# Saturn_Cartage.net
KiCad netlist of a schematic drawn in Altium Designer
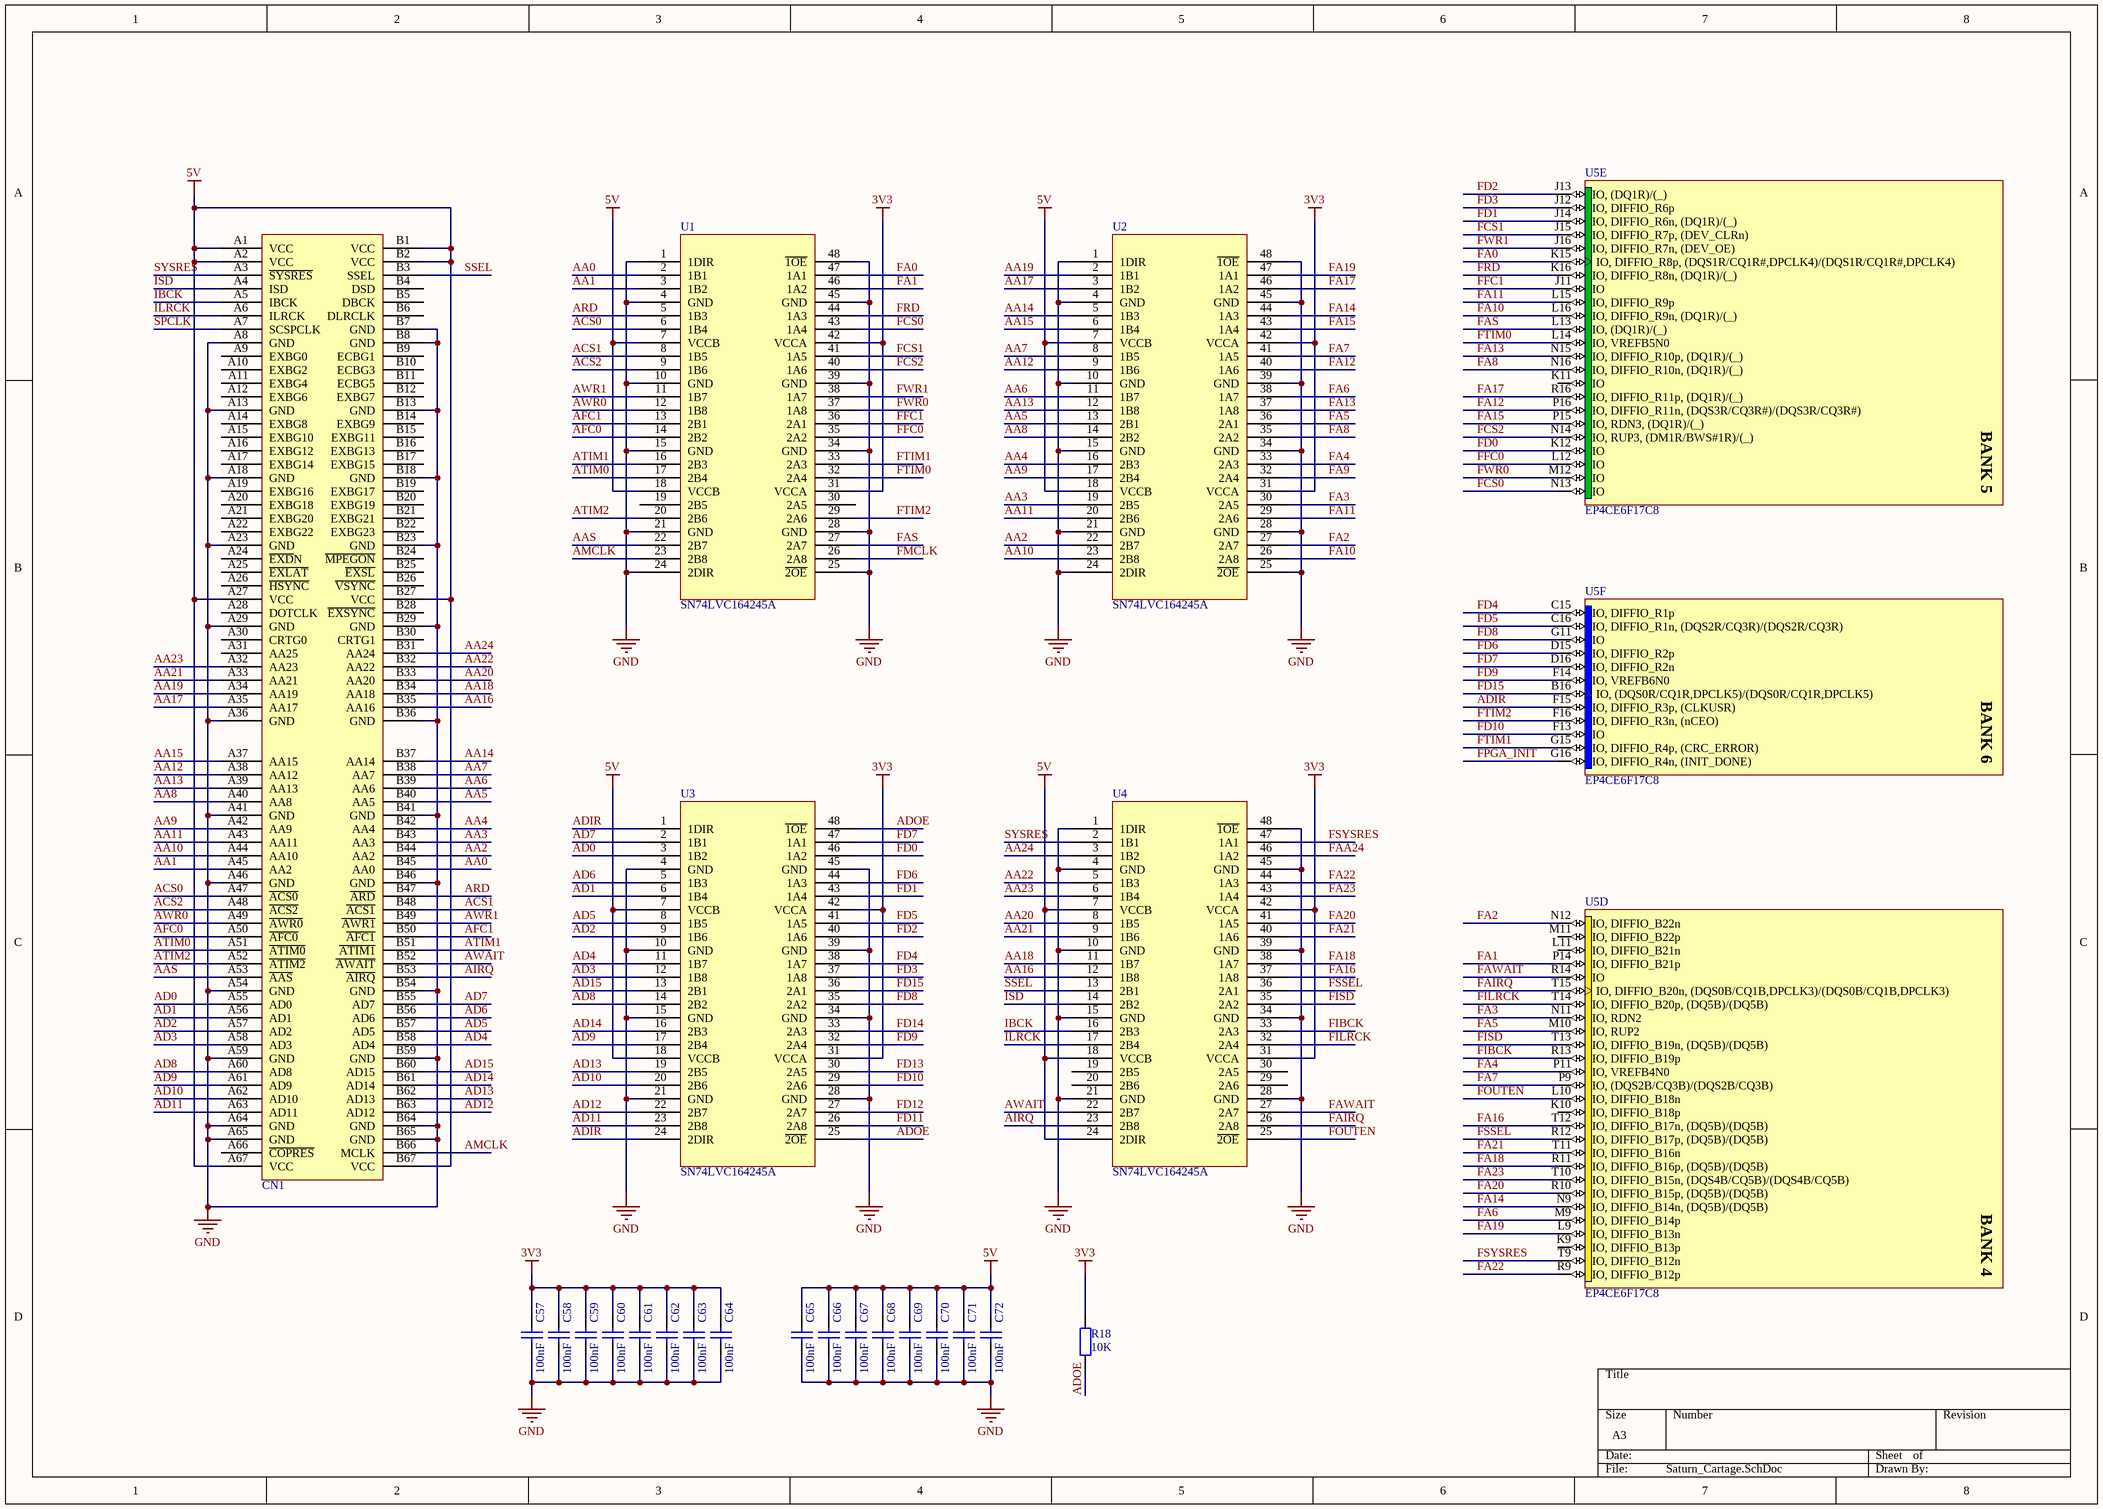
[diagram p0: Saturn_Cartage.SchDoc]

(export (version "E")
  (design (tool "Eeschema 10.0.6"))
  (components
    (comp (ref "C57")
      (value "100nF")
      (footprint "C0603")
      (description "Capacitor")
      (fields (field (name "PUBLISHER") "Altium Limited"))
      (libsource (lib "Miscellaneous Devices") (part "Cap"))
    )
    (comp (ref "C58")
      (value "100nF")
      (footprint "C0603")
      (description "Capacitor")
      (fields (field (name "PUBLISHER") "Altium Limited"))
      (libsource (lib "Miscellaneous Devices") (part "Cap"))
    )
    (comp (ref "C59")
      (value "100nF")
      (footprint "C0603")
      (description "Capacitor")
      (fields (field (name "PUBLISHER") "Altium Limited"))
      (libsource (lib "Miscellaneous Devices") (part "Cap"))
    )
    (comp (ref "C60")
      (value "100nF")
      (footprint "C0603")
      (description "Capacitor")
      (fields (field (name "PUBLISHER") "Altium Limited"))
      (libsource (lib "Miscellaneous Devices") (part "Cap"))
    )
    (comp (ref "C61")
      (value "100nF")
      (footprint "C0603")
      (description "Capacitor")
      (fields (field (name "PUBLISHER") "Altium Limited"))
      (libsource (lib "Miscellaneous Devices") (part "Cap"))
    )
    (comp (ref "C62")
      (value "100nF")
      (footprint "C0603")
      (description "Capacitor")
      (fields (field (name "PUBLISHER") "Altium Limited"))
      (libsource (lib "Miscellaneous Devices") (part "Cap"))
    )
    (comp (ref "C63")
      (value "100nF")
      (footprint "C0603")
      (description "Capacitor")
      (fields (field (name "PUBLISHER") "Altium Limited"))
      (libsource (lib "Miscellaneous Devices") (part "Cap"))
    )
    (comp (ref "C64")
      (value "100nF")
      (footprint "C0603")
      (description "Capacitor")
      (fields (field (name "PUBLISHER") "Altium Limited"))
      (libsource (lib "Miscellaneous Devices") (part "Cap"))
    )
    (comp (ref "C65")
      (value "100nF")
      (footprint "C0603")
      (description "Capacitor")
      (fields (field (name "PUBLISHER") "Altium Limited"))
      (libsource (lib "Miscellaneous Devices") (part "Cap"))
    )
    (comp (ref "C66")
      (value "100nF")
      (footprint "C0603")
      (description "Capacitor")
      (fields (field (name "PUBLISHER") "Altium Limited"))
      (libsource (lib "Miscellaneous Devices") (part "Cap"))
    )
    (comp (ref "C67")
      (value "100nF")
      (footprint "C0603")
      (description "Capacitor")
      (fields (field (name "PUBLISHER") "Altium Limited"))
      (libsource (lib "Miscellaneous Devices") (part "Cap"))
    )
    (comp (ref "C68")
      (value "100nF")
      (footprint "C0603")
      (description "Capacitor")
      (fields (field (name "PUBLISHER") "Altium Limited"))
      (libsource (lib "Miscellaneous Devices") (part "Cap"))
    )
    (comp (ref "C69")
      (value "100nF")
      (footprint "C0603")
      (description "Capacitor")
      (fields (field (name "PUBLISHER") "Altium Limited"))
      (libsource (lib "Miscellaneous Devices") (part "Cap"))
    )
    (comp (ref "C70")
      (value "100nF")
      (footprint "C0603")
      (description "Capacitor")
      (fields (field (name "PUBLISHER") "Altium Limited"))
      (libsource (lib "Miscellaneous Devices") (part "Cap"))
    )
    (comp (ref "C71")
      (value "100nF")
      (footprint "C0603")
      (description "Capacitor")
      (fields (field (name "PUBLISHER") "Altium Limited"))
      (libsource (lib "Miscellaneous Devices") (part "Cap"))
    )
    (comp (ref "C72")
      (value "100nF")
      (footprint "C0603")
      (description "Capacitor")
      (fields (field (name "PUBLISHER") "Altium Limited"))
      (libsource (lib "Miscellaneous Devices") (part "Cap"))
    )
    (comp (ref "CN1")
      (value "SaturnCartage")
      (footprint "Saturn_cart")
      (libsource (lib "ssmaster_1") (part "SaturnCartage"))
    )
    (comp (ref "R18")
      (value "10K")
      (footprint "R0603")
      (description "Resistor")
      (fields (field (name "PUBLISHER") "Altium Limited"))
      (libsource (lib "Miscellaneous Devices") (part "Res2"))
    )
    (comp (ref "U1")
      (value "SN74LVC164245A")
      (footprint "DGG048")
      (libsource (lib "ssmaster_1") (part "SN74LVC164245A"))
    )
    (comp (ref "U2")
      (value "SN74LVC164245A")
      (footprint "DGG048")
      (libsource (lib "ssmaster_1") (part "SN74LVC164245A"))
    )
    (comp (ref "U3")
      (value "SN74LVC164245A")
      (footprint "DGG048")
      (libsource (lib "ssmaster_1") (part "SN74LVC164245A"))
    )
    (comp (ref "U4")
      (value "SN74LVC164245A")
      (footprint "DGG048")
      (libsource (lib "ssmaster_1") (part "SN74LVC164245A"))
    )
    (comp (ref "U5")
      (value "EP4CE6F17C8")
      (footprint "FBGA256")
      (fields (field (name "PUBLISHER") "Altium Limited"))
      (libsource (lib "Altera Cyclone IV E") (part "EP4CE6F17C8"))
    )
  )
  (nets
    (net (code "1") (name "/AA0") (class "Default")
      (node (ref "CN1") (pin "B45") (pinfunction "AA0_B45") (pintype "passive"))
      (node (ref "U1") (pin "2") (pinfunction "1B1_2") (pintype "passive"))
    )
    (net (code "2") (name "/AA1") (class "Default")
      (node (ref "CN1") (pin "A45") (pinfunction "AA2_A45") (pintype "passive"))
      (node (ref "U1") (pin "3") (pinfunction "1B2_3") (pintype "passive"))
    )
    (net (code "3") (name "/AA2") (class "Default")
      (node (ref "CN1") (pin "B44") (pinfunction "AA2_B44") (pintype "passive"))
      (node (ref "U2") (pin "22") (pinfunction "2B7_22") (pintype "passive"))
    )
    (net (code "4") (name "/AA3") (class "Default")
      (node (ref "CN1") (pin "B43") (pinfunction "AA3_B43") (pintype "passive"))
      (node (ref "U2") (pin "19") (pinfunction "2B5_19") (pintype "passive"))
    )
    (net (code "5") (name "/AA4") (class "Default")
      (node (ref "CN1") (pin "B42") (pinfunction "AA4_B42") (pintype "passive"))
      (node (ref "U2") (pin "16") (pinfunction "2B3_16") (pintype "passive"))
    )
    (net (code "6") (name "/AA5") (class "Default")
      (node (ref "CN1") (pin "B40") (pinfunction "AA5_B40") (pintype "passive"))
      (node (ref "U2") (pin "13") (pinfunction "2B1_13") (pintype "passive"))
    )
    (net (code "7") (name "/AA6") (class "Default")
      (node (ref "CN1") (pin "B39") (pinfunction "AA6_B39") (pintype "passive"))
      (node (ref "U2") (pin "11") (pinfunction "1B7_11") (pintype "passive"))
    )
    (net (code "8") (name "/AA7") (class "Default")
      (node (ref "CN1") (pin "B38") (pinfunction "AA7_B38") (pintype "passive"))
      (node (ref "U2") (pin "8") (pinfunction "1B5_8") (pintype "passive"))
    )
    (net (code "9") (name "/AA8") (class "Default")
      (node (ref "CN1") (pin "A40") (pinfunction "AA8_A40") (pintype "passive"))
      (node (ref "U2") (pin "14") (pinfunction "2B2_14") (pintype "passive"))
    )
    (net (code "10") (name "/AA9") (class "Default")
      (node (ref "CN1") (pin "A42") (pinfunction "AA9_A42") (pintype "passive"))
      (node (ref "U2") (pin "17") (pinfunction "2B4_17") (pintype "passive"))
    )
    (net (code "11") (name "/AA10") (class "Default")
      (node (ref "CN1") (pin "A44") (pinfunction "AA10_A44") (pintype "passive"))
      (node (ref "U2") (pin "23") (pinfunction "2B8_23") (pintype "passive"))
    )
    (net (code "12") (name "/AA11") (class "Default")
      (node (ref "CN1") (pin "A43") (pinfunction "AA11_A43") (pintype "passive"))
      (node (ref "U2") (pin "20") (pinfunction "2B6_20") (pintype "passive"))
    )
    (net (code "13") (name "/AA12") (class "Default")
      (node (ref "CN1") (pin "A38") (pinfunction "AA12_A38") (pintype "passive"))
      (node (ref "U2") (pin "9") (pinfunction "1B6_9") (pintype "passive"))
    )
    (net (code "14") (name "/AA13") (class "Default")
      (node (ref "CN1") (pin "A39") (pinfunction "AA13_A39") (pintype "passive"))
      (node (ref "U2") (pin "12") (pinfunction "1B8_12") (pintype "passive"))
    )
    (net (code "15") (name "/AA14") (class "Default")
      (node (ref "CN1") (pin "B37") (pinfunction "AA14_B37") (pintype "passive"))
      (node (ref "U2") (pin "5") (pinfunction "1B3_5") (pintype "passive"))
    )
    (net (code "16") (name "/AA15") (class "Default")
      (node (ref "CN1") (pin "A37") (pinfunction "AA15_A37") (pintype "passive"))
      (node (ref "U2") (pin "6") (pinfunction "1B4_6") (pintype "passive"))
    )
    (net (code "17") (name "/AA16") (class "Default")
      (node (ref "CN1") (pin "B35") (pinfunction "AA16_B35") (pintype "passive"))
      (node (ref "U4") (pin "12") (pinfunction "1B8_12") (pintype "passive"))
    )
    (net (code "18") (name "/AA17") (class "Default")
      (node (ref "CN1") (pin "A35") (pinfunction "AA17_A35") (pintype "passive"))
      (node (ref "U2") (pin "3") (pinfunction "1B2_3") (pintype "passive"))
    )
    (net (code "19") (name "/AA18") (class "Default")
      (node (ref "CN1") (pin "B34") (pinfunction "AA18_B34") (pintype "passive"))
      (node (ref "U4") (pin "11") (pinfunction "1B7_11") (pintype "passive"))
    )
    (net (code "20") (name "/AA19") (class "Default")
      (node (ref "CN1") (pin "A34") (pinfunction "AA19_A34") (pintype "passive"))
      (node (ref "U2") (pin "2") (pinfunction "1B1_2") (pintype "passive"))
    )
    (net (code "21") (name "/AA20") (class "Default")
      (node (ref "CN1") (pin "B33") (pinfunction "AA20_B33") (pintype "passive"))
      (node (ref "U4") (pin "8") (pinfunction "1B5_8") (pintype "passive"))
    )
    (net (code "22") (name "/AA21") (class "Default")
      (node (ref "CN1") (pin "A33") (pinfunction "AA21_A33") (pintype "passive"))
      (node (ref "U4") (pin "9") (pinfunction "1B6_9") (pintype "passive"))
    )
    (net (code "23") (name "/AA22") (class "Default")
      (node (ref "CN1") (pin "B32") (pinfunction "AA22_B32") (pintype "passive"))
      (node (ref "U4") (pin "5") (pinfunction "1B3_5") (pintype "passive"))
    )
    (net (code "24") (name "/AA23") (class "Default")
      (node (ref "CN1") (pin "A32") (pinfunction "AA23_A32") (pintype "passive"))
      (node (ref "U4") (pin "6") (pinfunction "1B4_6") (pintype "passive"))
    )
    (net (code "25") (name "/AA24") (class "Default")
      (node (ref "CN1") (pin "B31") (pinfunction "AA24_B31") (pintype "passive"))
      (node (ref "U4") (pin "3") (pinfunction "1B2_3") (pintype "passive"))
    )
    (net (code "26") (name "/AAS") (class "Default")
      (node (ref "CN1") (pin "A53") (pinfunction "~{AAS}_A53") (pintype "passive"))
      (node (ref "U1") (pin "22") (pinfunction "2B7_22") (pintype "passive"))
    )
    (net (code "27") (name "/ACS0") (class "Default")
      (node (ref "CN1") (pin "A47") (pinfunction "~{ACS0}_A47") (pintype "passive"))
      (node (ref "U1") (pin "6") (pinfunction "1B4_6") (pintype "passive"))
    )
    (net (code "28") (name "/ACS1") (class "Default")
      (node (ref "CN1") (pin "B48") (pinfunction "~{ACS1}_B48") (pintype "passive"))
      (node (ref "U1") (pin "8") (pinfunction "1B5_8") (pintype "passive"))
    )
    (net (code "29") (name "/ACS2") (class "Default")
      (node (ref "CN1") (pin "A48") (pinfunction "~{ACS2}_A48") (pintype "passive"))
      (node (ref "U1") (pin "9") (pinfunction "1B6_9") (pintype "passive"))
    )
    (net (code "30") (name "/AD0") (class "Default")
      (node (ref "CN1") (pin "A55") (pinfunction "AD0_A55") (pintype "passive"))
      (node (ref "U3") (pin "3") (pinfunction "1B2_3") (pintype "passive"))
    )
    (net (code "31") (name "/AD1") (class "Default")
      (node (ref "CN1") (pin "A56") (pinfunction "AD1_A56") (pintype "passive"))
      (node (ref "U3") (pin "6") (pinfunction "1B4_6") (pintype "passive"))
    )
    (net (code "32") (name "/AD2") (class "Default")
      (node (ref "CN1") (pin "A57") (pinfunction "AD2_A57") (pintype "passive"))
      (node (ref "U3") (pin "9") (pinfunction "1B6_9") (pintype "passive"))
    )
    (net (code "33") (name "/AD3") (class "Default")
      (node (ref "CN1") (pin "A58") (pinfunction "AD3_A58") (pintype "passive"))
      (node (ref "U3") (pin "12") (pinfunction "1B8_12") (pintype "passive"))
    )
    (net (code "34") (name "/AD4") (class "Default")
      (node (ref "CN1") (pin "B58") (pinfunction "AD4_B58") (pintype "passive"))
      (node (ref "U3") (pin "11") (pinfunction "1B7_11") (pintype "passive"))
    )
    (net (code "35") (name "/AD5") (class "Default")
      (node (ref "CN1") (pin "B57") (pinfunction "AD5_B57") (pintype "passive"))
      (node (ref "U3") (pin "8") (pinfunction "1B5_8") (pintype "passive"))
    )
    (net (code "36") (name "/AD6") (class "Default")
      (node (ref "CN1") (pin "B56") (pinfunction "AD6_B56") (pintype "passive"))
      (node (ref "U3") (pin "5") (pinfunction "1B3_5") (pintype "passive"))
    )
    (net (code "37") (name "/AD7") (class "Default")
      (node (ref "CN1") (pin "B55") (pinfunction "AD7_B55") (pintype "passive"))
      (node (ref "U3") (pin "2") (pinfunction "1B1_2") (pintype "passive"))
    )
    (net (code "38") (name "/AD8") (class "Default")
      (node (ref "CN1") (pin "A60") (pinfunction "AD8_A60") (pintype "passive"))
      (node (ref "U3") (pin "14") (pinfunction "2B2_14") (pintype "passive"))
    )
    (net (code "39") (name "/AD9") (class "Default")
      (node (ref "CN1") (pin "A61") (pinfunction "AD9_A61") (pintype "passive"))
      (node (ref "U3") (pin "17") (pinfunction "2B4_17") (pintype "passive"))
    )
    (net (code "40") (name "/AD10") (class "Default")
      (node (ref "CN1") (pin "A62") (pinfunction "AD10_A62") (pintype "passive"))
      (node (ref "U3") (pin "20") (pinfunction "2B6_20") (pintype "passive"))
    )
    (net (code "41") (name "/AD11") (class "Default")
      (node (ref "CN1") (pin "A63") (pinfunction "AD11_A63") (pintype "passive"))
      (node (ref "U3") (pin "23") (pinfunction "2B8_23") (pintype "passive"))
    )
    (net (code "42") (name "/AD12") (class "Default")
      (node (ref "CN1") (pin "B63") (pinfunction "AD12_B63") (pintype "passive"))
      (node (ref "U3") (pin "22") (pinfunction "2B7_22") (pintype "passive"))
    )
    (net (code "43") (name "/AD13") (class "Default")
      (node (ref "CN1") (pin "B62") (pinfunction "AD13_B62") (pintype "passive"))
      (node (ref "U3") (pin "19") (pinfunction "2B5_19") (pintype "passive"))
    )
    (net (code "44") (name "/AD14") (class "Default")
      (node (ref "CN1") (pin "B61") (pinfunction "AD14_B61") (pintype "passive"))
      (node (ref "U3") (pin "16") (pinfunction "2B3_16") (pintype "passive"))
    )
    (net (code "45") (name "/AD15") (class "Default")
      (node (ref "CN1") (pin "B60") (pinfunction "AD15_B60") (pintype "passive"))
      (node (ref "U3") (pin "13") (pinfunction "2B1_13") (pintype "passive"))
    )
    (net (code "46") (name "/ADIR") (class "Default")
      (node (ref "U3") (pin "1") (pinfunction "1DIR_1") (pintype "passive"))
      (node (ref "U3") (pin "24") (pinfunction "2DIR_24") (pintype "passive"))
      (node (ref "U5") (pin "F15") (pinfunction "IO,_DIFFIO_R3p,_(CLKUSR)_F15") (pintype "bidirectional"))
    )
    (net (code "47") (name "/ADOE") (class "Default")
      (node (ref "R18") (pin "1") (pinfunction "1_1") (pintype "passive"))
      (node (ref "U3") (pin "25") (pinfunction "~{2OE}_25") (pintype "passive"))
      (node (ref "U3") (pin "48") (pinfunction "~{1OE}_48") (pintype "passive"))
    )
    (net (code "48") (name "/AFC0") (class "Default")
      (node (ref "CN1") (pin "A50") (pinfunction "~{AFC0}_A50") (pintype "passive"))
      (node (ref "U1") (pin "14") (pinfunction "2B2_14") (pintype "passive"))
    )
    (net (code "49") (name "/AFC1") (class "Default")
      (node (ref "CN1") (pin "B50") (pinfunction "~{AFC1}_B50") (pintype "passive"))
      (node (ref "U1") (pin "13") (pinfunction "2B1_13") (pintype "passive"))
    )
    (net (code "50") (name "/AIRQ") (class "Default")
      (node (ref "CN1") (pin "B53") (pinfunction "~{AIRQ}_B53") (pintype "passive"))
      (node (ref "U4") (pin "23") (pinfunction "2B8_23") (pintype "passive"))
    )
    (net (code "51") (name "/AMCLK") (class "Default")
      (node (ref "CN1") (pin "B66") (pinfunction "MCLK_B66") (pintype "passive"))
      (node (ref "U1") (pin "23") (pinfunction "2B8_23") (pintype "passive"))
    )
    (net (code "52") (name "/ARD") (class "Default")
      (node (ref "CN1") (pin "B47") (pinfunction "~{ARD}_B47") (pintype "passive"))
      (node (ref "U1") (pin "5") (pinfunction "1B3_5") (pintype "passive"))
    )
    (net (code "53") (name "/ATIM0") (class "Default")
      (node (ref "CN1") (pin "A51") (pinfunction "~{ATIM0}_A51") (pintype "passive"))
      (node (ref "U1") (pin "17") (pinfunction "2B4_17") (pintype "passive"))
    )
    (net (code "54") (name "/ATIM1") (class "Default")
      (node (ref "CN1") (pin "B51") (pinfunction "~{ATIM1}_B51") (pintype "passive"))
      (node (ref "U1") (pin "16") (pinfunction "2B3_16") (pintype "passive"))
    )
    (net (code "55") (name "/ATIM2") (class "Default")
      (node (ref "CN1") (pin "A52") (pinfunction "~{ATIM2}_A52") (pintype "passive"))
      (node (ref "U1") (pin "20") (pinfunction "2B6_20") (pintype "passive"))
    )
    (net (code "56") (name "/AWAIT") (class "Default")
      (node (ref "CN1") (pin "B52") (pinfunction "~{AWAIT}_B52") (pintype "passive"))
      (node (ref "U4") (pin "22") (pinfunction "2B7_22") (pintype "passive"))
    )
    (net (code "57") (name "/AWR0") (class "Default")
      (node (ref "CN1") (pin "A49") (pinfunction "~{AWR0}_A49") (pintype "passive"))
      (node (ref "U1") (pin "12") (pinfunction "1B8_12") (pintype "passive"))
    )
    (net (code "58") (name "/AWR1") (class "Default")
      (node (ref "CN1") (pin "B49") (pinfunction "~{AWR1}_B49") (pintype "passive"))
      (node (ref "U1") (pin "11") (pinfunction "1B7_11") (pintype "passive"))
    )
    (net (code "59") (name "/FA0") (class "Default")
      (node (ref "U1") (pin "47") (pinfunction "1A1_47") (pintype "passive"))
      (node (ref "U5") (pin "K15") (pinfunction "IO,_DIFFIO_R8p,_(DQS1R/CQ1R#,DPCLK4)/(DQS1R/CQ1R#,DPCLK4)_K15") (pintype "bidirectional"))
    )
    (net (code "60") (name "/FA1") (class "Default")
      (node (ref "U1") (pin "46") (pinfunction "1A2_46") (pintype "power_in"))
      (node (ref "U5") (pin "P14") (pinfunction "IO,_DIFFIO_B21p_P14") (pintype "bidirectional"))
    )
    (net (code "61") (name "/FA2") (class "Default")
      (node (ref "U2") (pin "27") (pinfunction "2A7_27") (pintype "passive"))
      (node (ref "U5") (pin "N12") (pinfunction "IO,_DIFFIO_B22n_N12") (pintype "bidirectional"))
    )
    (net (code "62") (name "/FA3") (class "Default")
      (node (ref "U2") (pin "30") (pinfunction "2A5_30") (pintype "passive"))
      (node (ref "U5") (pin "N11") (pinfunction "IO,_RDN2_N11") (pintype "bidirectional"))
    )
    (net (code "63") (name "/FA4") (class "Default")
      (node (ref "U2") (pin "33") (pinfunction "2A3_33") (pintype "passive"))
      (node (ref "U5") (pin "P11") (pinfunction "IO,_VREFB4N0_P11") (pintype "bidirectional"))
    )
    (net (code "64") (name "/FA5") (class "Default")
      (node (ref "U2") (pin "36") (pinfunction "2A1_36") (pintype "passive"))
      (node (ref "U5") (pin "M10") (pinfunction "IO,_RUP2_M10") (pintype "bidirectional"))
    )
    (net (code "65") (name "/FA6") (class "Default")
      (node (ref "U2") (pin "38") (pinfunction "1A7_38") (pintype "passive"))
      (node (ref "U5") (pin "M9") (pinfunction "IO,_DIFFIO_B14p_M9") (pintype "bidirectional"))
    )
    (net (code "66") (name "/FA7") (class "Default")
      (node (ref "U2") (pin "41") (pinfunction "1A5_41") (pintype "passive"))
      (node (ref "U5") (pin "P9") (pinfunction "IO,_(DQS2B/CQ3B)/(DQS2B/CQ3B)_P9") (pintype "bidirectional"))
    )
    (net (code "67") (name "/FA8") (class "Default")
      (node (ref "U2") (pin "35") (pinfunction "2A2_35") (pintype "passive"))
      (node (ref "U5") (pin "N16") (pinfunction "IO,_DIFFIO_R10n,_(DQ1R)/(_)_N16") (pintype "bidirectional"))
    )
    (net (code "68") (name "/FA9") (class "Default")
      (node (ref "U2") (pin "32") (pinfunction "2A4_32") (pintype "passive"))
    )
    (net (code "69") (name "/FA10") (class "Default")
      (node (ref "U2") (pin "26") (pinfunction "2A8_26") (pintype "passive"))
      (node (ref "U5") (pin "L16") (pinfunction "IO,_DIFFIO_R9n,_(DQ1R)/(_)_L16") (pintype "bidirectional"))
    )
    (net (code "70") (name "/FA11") (class "Default")
      (node (ref "U2") (pin "29") (pinfunction "2A6_29") (pintype "passive"))
      (node (ref "U5") (pin "L15") (pinfunction "IO,_DIFFIO_R9p_L15") (pintype "bidirectional"))
    )
    (net (code "71") (name "/FA12") (class "Default")
      (node (ref "U2") (pin "40") (pinfunction "1A6_40") (pintype "passive"))
      (node (ref "U5") (pin "P16") (pinfunction "IO,_DIFFIO_R11n,_(DQS3R/CQ3R#)/(DQS3R/CQ3R#)_P16") (pintype "bidirectional"))
    )
    (net (code "72") (name "/FA13") (class "Default")
      (node (ref "U2") (pin "37") (pinfunction "1A8_37") (pintype "passive"))
      (node (ref "U5") (pin "N15") (pinfunction "IO,_DIFFIO_R10p,_(DQ1R)/(_)_N15") (pintype "bidirectional"))
    )
    (net (code "73") (name "/FA14") (class "Default")
      (node (ref "U2") (pin "44") (pinfunction "1A3_44") (pintype "passive"))
      (node (ref "U5") (pin "N9") (pinfunction "IO,_DIFFIO_B14n,_(DQ5B)/(DQ5B)_N9") (pintype "bidirectional"))
    )
    (net (code "74") (name "/FA15") (class "Default")
      (node (ref "U2") (pin "43") (pinfunction "1A4_43") (pintype "passive"))
      (node (ref "U5") (pin "P15") (pinfunction "IO,_RDN3,_(DQ1R)/(_)_P15") (pintype "bidirectional"))
    )
    (net (code "75") (name "/FA16") (class "Default")
      (node (ref "U4") (pin "37") (pinfunction "1A8_37") (pintype "passive"))
      (node (ref "U5") (pin "T12") (pinfunction "IO,_DIFFIO_B17n,_(DQ5B)/(DQ5B)_T12") (pintype "bidirectional"))
    )
    (net (code "76") (name "/FA17") (class "Default")
      (node (ref "U2") (pin "46") (pinfunction "1A2_46") (pintype "power_in"))
      (node (ref "U5") (pin "R16") (pinfunction "IO,_DIFFIO_R11p,_(DQ1R)/(_)_R16") (pintype "bidirectional"))
    )
    (net (code "77") (name "/FA18") (class "Default")
      (node (ref "U4") (pin "38") (pinfunction "1A7_38") (pintype "passive"))
      (node (ref "U5") (pin "R11") (pinfunction "IO,_DIFFIO_B16p,_(DQ5B)/(DQ5B)_R11") (pintype "bidirectional"))
    )
    (net (code "78") (name "/FA19") (class "Default")
      (node (ref "U2") (pin "47") (pinfunction "1A1_47") (pintype "passive"))
      (node (ref "U5") (pin "L9") (pinfunction "IO,_DIFFIO_B13n_L9") (pintype "bidirectional"))
    )
    (net (code "79") (name "/FA20") (class "Default")
      (node (ref "U4") (pin "41") (pinfunction "1A5_41") (pintype "passive"))
      (node (ref "U5") (pin "R10") (pinfunction "IO,_DIFFIO_B15p,_(DQ5B)/(DQ5B)_R10") (pintype "bidirectional"))
    )
    (net (code "80") (name "/FA21") (class "Default")
      (node (ref "U4") (pin "40") (pinfunction "1A6_40") (pintype "passive"))
      (node (ref "U5") (pin "T11") (pinfunction "IO,_DIFFIO_B16n_T11") (pintype "bidirectional"))
    )
    (net (code "81") (name "/FA22") (class "Default")
      (node (ref "U4") (pin "44") (pinfunction "1A3_44") (pintype "passive"))
      (node (ref "U5") (pin "R9") (pinfunction "IO,_DIFFIO_B12p_R9") (pintype "bidirectional"))
    )
    (net (code "82") (name "/FA23") (class "Default")
      (node (ref "U4") (pin "43") (pinfunction "1A4_43") (pintype "passive"))
      (node (ref "U5") (pin "T10") (pinfunction "IO,_DIFFIO_B15n,_(DQS4B/CQ5B)/(DQS4B/CQ5B)_T10") (pintype "bidirectional"))
    )
    (net (code "83") (name "/FAA24") (class "Default")
      (node (ref "U4") (pin "46") (pinfunction "1A2_46") (pintype "power_in"))
    )
    (net (code "84") (name "/FAIRQ") (class "Default")
      (node (ref "U4") (pin "26") (pinfunction "2A8_26") (pintype "passive"))
      (node (ref "U5") (pin "T15") (pinfunction "IO,_DIFFIO_B20n,_(DQS0B/CQ1B,DPCLK3)/(DQS0B/CQ1B,DPCLK3)_T15") (pintype "bidirectional"))
    )
    (net (code "85") (name "/FAS") (class "Default")
      (node (ref "U1") (pin "27") (pinfunction "2A7_27") (pintype "passive"))
      (node (ref "U5") (pin "L13") (pinfunction "IO,_(DQ1R)/(_)_L13") (pintype "bidirectional"))
    )
    (net (code "86") (name "/FAWAIT") (class "Default")
      (node (ref "U4") (pin "27") (pinfunction "2A7_27") (pintype "passive"))
      (node (ref "U5") (pin "R14") (pinfunction "IO_R14") (pintype "bidirectional"))
    )
    (net (code "87") (name "/FCS0") (class "Default")
      (node (ref "U1") (pin "43") (pinfunction "1A4_43") (pintype "passive"))
      (node (ref "U5") (pin "N13") (pinfunction "IO_N13") (pintype "bidirectional"))
    )
    (net (code "88") (name "/FCS1") (class "Default")
      (node (ref "U1") (pin "41") (pinfunction "1A5_41") (pintype "passive"))
      (node (ref "U5") (pin "J15") (pinfunction "IO,_DIFFIO_R7p,_(DEV_CLRn)_J15") (pintype "bidirectional"))
    )
    (net (code "89") (name "/FCS2") (class "Default")
      (node (ref "U1") (pin "40") (pinfunction "1A6_40") (pintype "passive"))
      (node (ref "U5") (pin "N14") (pinfunction "IO,_RUP3,_(DM1R/BWS#1R)/(_)_N14") (pintype "bidirectional"))
    )
    (net (code "90") (name "/FD0") (class "Default")
      (node (ref "U3") (pin "46") (pinfunction "1A2_46") (pintype "power_in"))
      (node (ref "U5") (pin "K12") (pinfunction "IO_K12") (pintype "bidirectional"))
    )
    (net (code "91") (name "/FD1") (class "Default")
      (node (ref "U3") (pin "43") (pinfunction "1A4_43") (pintype "passive"))
      (node (ref "U5") (pin "J14") (pinfunction "IO,_DIFFIO_R6n,_(DQ1R)/(_)_J14") (pintype "bidirectional"))
    )
    (net (code "92") (name "/FD2") (class "Default")
      (node (ref "U3") (pin "40") (pinfunction "1A6_40") (pintype "passive"))
      (node (ref "U5") (pin "J13") (pinfunction "IO,_(DQ1R)/(_)_J13") (pintype "bidirectional"))
    )
    (net (code "93") (name "/FD3") (class "Default")
      (node (ref "U3") (pin "37") (pinfunction "1A8_37") (pintype "passive"))
      (node (ref "U5") (pin "J12") (pinfunction "IO,_DIFFIO_R6p_J12") (pintype "bidirectional"))
    )
    (net (code "94") (name "/FD4") (class "Default")
      (node (ref "U3") (pin "38") (pinfunction "1A7_38") (pintype "passive"))
      (node (ref "U5") (pin "C15") (pinfunction "IO,_DIFFIO_R1p_C15") (pintype "bidirectional"))
    )
    (net (code "95") (name "/FD5") (class "Default")
      (node (ref "U3") (pin "41") (pinfunction "1A5_41") (pintype "passive"))
      (node (ref "U5") (pin "C16") (pinfunction "IO,_DIFFIO_R1n,_(DQS2R/CQ3R)/(DQS2R/CQ3R)_C16") (pintype "bidirectional"))
    )
    (net (code "96") (name "/FD6") (class "Default")
      (node (ref "U3") (pin "44") (pinfunction "1A3_44") (pintype "passive"))
      (node (ref "U5") (pin "D15") (pinfunction "IO,_DIFFIO_R2p_D15") (pintype "bidirectional"))
    )
    (net (code "97") (name "/FD7") (class "Default")
      (node (ref "U3") (pin "47") (pinfunction "1A1_47") (pintype "passive"))
      (node (ref "U5") (pin "D16") (pinfunction "IO,_DIFFIO_R2n_D16") (pintype "bidirectional"))
    )
    (net (code "98") (name "/FD8") (class "Default")
      (node (ref "U3") (pin "35") (pinfunction "2A2_35") (pintype "passive"))
      (node (ref "U5") (pin "G11") (pinfunction "IO_G11") (pintype "bidirectional"))
    )
    (net (code "99") (name "/FD9") (class "Default")
      (node (ref "U3") (pin "32") (pinfunction "2A4_32") (pintype "passive"))
      (node (ref "U5") (pin "F14") (pinfunction "IO,_VREFB6N0_F14") (pintype "bidirectional"))
    )
    (net (code "100") (name "/FD10") (class "Default")
      (node (ref "U3") (pin "29") (pinfunction "2A6_29") (pintype "passive"))
      (node (ref "U5") (pin "F13") (pinfunction "IO_F13") (pintype "bidirectional"))
    )
    (net (code "101") (name "/FD11") (class "Default")
      (node (ref "U3") (pin "26") (pinfunction "2A8_26") (pintype "passive"))
    )
    (net (code "102") (name "/FD12") (class "Default")
      (node (ref "U3") (pin "27") (pinfunction "2A7_27") (pintype "passive"))
    )
    (net (code "103") (name "/FD13") (class "Default")
      (node (ref "U3") (pin "30") (pinfunction "2A5_30") (pintype "passive"))
    )
    (net (code "104") (name "/FD14") (class "Default")
      (node (ref "U3") (pin "33") (pinfunction "2A3_33") (pintype "passive"))
    )
    (net (code "105") (name "/FD15") (class "Default")
      (node (ref "U3") (pin "36") (pinfunction "2A1_36") (pintype "passive"))
      (node (ref "U5") (pin "B16") (pinfunction "IO,_(DQS0R/CQ1R,DPCLK5)/(DQS0R/CQ1R,DPCLK5)_B16") (pintype "bidirectional"))
    )
    (net (code "106") (name "/FFC0") (class "Default")
      (node (ref "U1") (pin "35") (pinfunction "2A2_35") (pintype "passive"))
      (node (ref "U5") (pin "L12") (pinfunction "IO_L12") (pintype "bidirectional"))
    )
    (net (code "107") (name "/FFC1") (class "Default")
      (node (ref "U1") (pin "36") (pinfunction "2A1_36") (pintype "passive"))
      (node (ref "U5") (pin "J11") (pinfunction "IO_J11") (pintype "bidirectional"))
    )
    (net (code "108") (name "/FIBCK") (class "Default")
      (node (ref "U4") (pin "33") (pinfunction "2A3_33") (pintype "passive"))
      (node (ref "U5") (pin "R13") (pinfunction "IO,_DIFFIO_B19p_R13") (pintype "bidirectional"))
    )
    (net (code "109") (name "/FILRCK") (class "Default")
      (node (ref "U4") (pin "32") (pinfunction "2A4_32") (pintype "passive"))
      (node (ref "U5") (pin "T14") (pinfunction "IO,_DIFFIO_B20p,_(DQ5B)/(DQ5B)_T14") (pintype "bidirectional"))
    )
    (net (code "110") (name "/FISD") (class "Default")
      (node (ref "U4") (pin "35") (pinfunction "2A2_35") (pintype "passive"))
      (node (ref "U5") (pin "T13") (pinfunction "IO,_DIFFIO_B19n,_(DQ5B)/(DQ5B)_T13") (pintype "bidirectional"))
    )
    (net (code "111") (name "/FMCLK") (class "Default")
      (node (ref "U1") (pin "26") (pinfunction "2A8_26") (pintype "passive"))
    )
    (net (code "112") (name "/FOUTEN") (class "Default")
      (node (ref "U4") (pin "25") (pinfunction "~{2OE}_25") (pintype "passive"))
      (node (ref "U5") (pin "L10") (pinfunction "IO,_DIFFIO_B18n_L10") (pintype "bidirectional"))
    )
    (net (code "113") (name "/FPGA_INIT") (class "Default")
      (node (ref "U5") (pin "G16") (pinfunction "IO,_DIFFIO_R4n,_(INIT_DONE)_G16") (pintype "bidirectional"))
    )
    (net (code "114") (name "/FRD") (class "Default")
      (node (ref "U1") (pin "44") (pinfunction "1A3_44") (pintype "passive"))
      (node (ref "U5") (pin "K16") (pinfunction "IO,_DIFFIO_R8n,_(DQ1R)/(_)_K16") (pintype "bidirectional"))
    )
    (net (code "115") (name "/FSSEL") (class "Default")
      (node (ref "U4") (pin "36") (pinfunction "2A1_36") (pintype "passive"))
      (node (ref "U5") (pin "R12") (pinfunction "IO,_DIFFIO_B17p,_(DQ5B)/(DQ5B)_R12") (pintype "bidirectional"))
    )
    (net (code "116") (name "/FSYSRES") (class "Default")
      (node (ref "U4") (pin "47") (pinfunction "1A1_47") (pintype "passive"))
      (node (ref "U5") (pin "T9") (pinfunction "IO,_DIFFIO_B12n_T9") (pintype "bidirectional"))
    )
    (net (code "117") (name "/FTIM0") (class "Default")
      (node (ref "U1") (pin "32") (pinfunction "2A4_32") (pintype "passive"))
      (node (ref "U5") (pin "L14") (pinfunction "IO,_VREFB5N0_L14") (pintype "bidirectional"))
    )
    (net (code "118") (name "/FTIM1") (class "Default")
      (node (ref "U1") (pin "33") (pinfunction "2A3_33") (pintype "passive"))
      (node (ref "U5") (pin "G15") (pinfunction "IO,_DIFFIO_R4p,_(CRC_ERROR)_G15") (pintype "bidirectional"))
    )
    (net (code "119") (name "/FTIM2") (class "Default")
      (node (ref "U1") (pin "29") (pinfunction "2A6_29") (pintype "passive"))
      (node (ref "U5") (pin "F16") (pinfunction "IO,_DIFFIO_R3n,_(nCEO)_F16") (pintype "bidirectional"))
    )
    (net (code "120") (name "/FWR0") (class "Default")
      (node (ref "U1") (pin "37") (pinfunction "1A8_37") (pintype "passive"))
      (node (ref "U5") (pin "M12") (pinfunction "IO_M12") (pintype "bidirectional"))
    )
    (net (code "121") (name "/FWR1") (class "Default")
      (node (ref "U1") (pin "38") (pinfunction "1A7_38") (pintype "passive"))
      (node (ref "U5") (pin "J16") (pinfunction "IO,_DIFFIO_R7n,_(DEV_OE)_J16") (pintype "bidirectional"))
    )
    (net (code "122") (name "/IBCK") (class "Default")
      (node (ref "CN1") (pin "A5") (pinfunction "IBCK_A5") (pintype "passive"))
      (node (ref "U4") (pin "16") (pinfunction "2B3_16") (pintype "passive"))
    )
    (net (code "123") (name "/ILRCK") (class "Default")
      (node (ref "CN1") (pin "A6") (pinfunction "ILRCK_A6") (pintype "passive"))
      (node (ref "U4") (pin "17") (pinfunction "2B4_17") (pintype "passive"))
    )
    (net (code "124") (name "/ISD") (class "Default")
      (node (ref "CN1") (pin "A4") (pinfunction "ISD_A4") (pintype "passive"))
      (node (ref "U4") (pin "14") (pinfunction "2B2_14") (pintype "passive"))
    )
    (net (code "125") (name "/SPCLK") (class "Default")
      (node (ref "CN1") (pin "A7") (pinfunction "SCSPCLK_A7") (pintype "passive"))
    )
    (net (code "126") (name "/SSEL") (class "Default")
      (node (ref "CN1") (pin "B3") (pinfunction "SSEL_B3") (pintype "passive"))
      (node (ref "U4") (pin "13") (pinfunction "2B1_13") (pintype "passive"))
    )
    (net (code "127") (name "/SYSRES") (class "Default")
      (node (ref "CN1") (pin "A3") (pinfunction "~{SYSRES}_A3") (pintype "passive"))
      (node (ref "U4") (pin "2") (pinfunction "1B1_2") (pintype "passive"))
    )
    (net (code "128") (name "3V3") (class "Default")
      (node (ref "C57") (pin "2") (pinfunction "2_2") (pintype "passive"))
      (node (ref "C58") (pin "2") (pinfunction "2_2") (pintype "passive"))
      (node (ref "C59") (pin "2") (pinfunction "2_2") (pintype "passive"))
      (node (ref "C60") (pin "2") (pinfunction "2_2") (pintype "passive"))
      (node (ref "C61") (pin "2") (pinfunction "2_2") (pintype "passive"))
      (node (ref "C62") (pin "2") (pinfunction "2_2") (pintype "passive"))
      (node (ref "C63") (pin "2") (pinfunction "2_2") (pintype "passive"))
      (node (ref "C64") (pin "2") (pinfunction "2_2") (pintype "passive"))
      (node (ref "R18") (pin "2") (pinfunction "2_2") (pintype "passive"))
      (node (ref "U1") (pin "31") (pinfunction "VCCA_31") (pintype "power_in"))
      (node (ref "U1") (pin "42") (pinfunction "VCCA_42") (pintype "power_in"))
      (node (ref "U2") (pin "31") (pinfunction "VCCA_31") (pintype "power_in"))
      (node (ref "U2") (pin "42") (pinfunction "VCCA_42") (pintype "power_in"))
      (node (ref "U3") (pin "31") (pinfunction "VCCA_31") (pintype "power_in"))
      (node (ref "U3") (pin "42") (pinfunction "VCCA_42") (pintype "power_in"))
      (node (ref "U4") (pin "31") (pinfunction "VCCA_31") (pintype "power_in"))
      (node (ref "U4") (pin "42") (pinfunction "VCCA_42") (pintype "power_in"))
    )
    (net (code "129") (name "5V") (class "Default")
      (node (ref "C65") (pin "2") (pinfunction "2_2") (pintype "passive"))
      (node (ref "C66") (pin "2") (pinfunction "2_2") (pintype "passive"))
      (node (ref "C67") (pin "2") (pinfunction "2_2") (pintype "passive"))
      (node (ref "C68") (pin "2") (pinfunction "2_2") (pintype "passive"))
      (node (ref "C69") (pin "2") (pinfunction "2_2") (pintype "passive"))
      (node (ref "C70") (pin "2") (pinfunction "2_2") (pintype "passive"))
      (node (ref "C71") (pin "2") (pinfunction "2_2") (pintype "passive"))
      (node (ref "C72") (pin "2") (pinfunction "2_2") (pintype "passive"))
      (node (ref "CN1") (pin "A1") (pinfunction "VCC_A1") (pintype "passive"))
      (node (ref "CN1") (pin "A2") (pinfunction "VCC_A2") (pintype "passive"))
      (node (ref "CN1") (pin "A27") (pinfunction "VCC_A27") (pintype "passive"))
      (node (ref "CN1") (pin "A67") (pinfunction "VCC_A67") (pintype "passive"))
      (node (ref "CN1") (pin "B1") (pinfunction "VCC_B1") (pintype "passive"))
      (node (ref "CN1") (pin "B2") (pinfunction "VCC_B2") (pintype "passive"))
      (node (ref "CN1") (pin "B27") (pinfunction "VCC_B27") (pintype "passive"))
      (node (ref "CN1") (pin "B67") (pinfunction "VCC_B67") (pintype "passive"))
      (node (ref "U1") (pin "18") (pinfunction "VCCB_18") (pintype "power_in"))
      (node (ref "U1") (pin "7") (pinfunction "VCCB_7") (pintype "power_in"))
      (node (ref "U2") (pin "18") (pinfunction "VCCB_18") (pintype "power_in"))
      (node (ref "U2") (pin "7") (pinfunction "VCCB_7") (pintype "power_in"))
      (node (ref "U3") (pin "18") (pinfunction "VCCB_18") (pintype "power_in"))
      (node (ref "U3") (pin "7") (pinfunction "VCCB_7") (pintype "power_in"))
      (node (ref "U4") (pin "18") (pinfunction "VCCB_18") (pintype "power_in"))
      (node (ref "U4") (pin "24") (pinfunction "2DIR_24") (pintype "passive"))
      (node (ref "U4") (pin "7") (pinfunction "VCCB_7") (pintype "power_in"))
    )
    (net (code "130") (name "GND") (class "Default")
      (node (ref "C57") (pin "1") (pinfunction "1_1") (pintype "passive"))
      (node (ref "C58") (pin "1") (pinfunction "1_1") (pintype "passive"))
      (node (ref "C59") (pin "1") (pinfunction "1_1") (pintype "passive"))
      (node (ref "C60") (pin "1") (pinfunction "1_1") (pintype "passive"))
      (node (ref "C61") (pin "1") (pinfunction "1_1") (pintype "passive"))
      (node (ref "C62") (pin "1") (pinfunction "1_1") (pintype "passive"))
      (node (ref "C63") (pin "1") (pinfunction "1_1") (pintype "passive"))
      (node (ref "C64") (pin "1") (pinfunction "1_1") (pintype "passive"))
      (node (ref "C65") (pin "1") (pinfunction "1_1") (pintype "passive"))
      (node (ref "C66") (pin "1") (pinfunction "1_1") (pintype "passive"))
      (node (ref "C67") (pin "1") (pinfunction "1_1") (pintype "passive"))
      (node (ref "C68") (pin "1") (pinfunction "1_1") (pintype "passive"))
      (node (ref "C69") (pin "1") (pinfunction "1_1") (pintype "passive"))
      (node (ref "C70") (pin "1") (pinfunction "1_1") (pintype "passive"))
      (node (ref "C71") (pin "1") (pinfunction "1_1") (pintype "passive"))
      (node (ref "C72") (pin "1") (pinfunction "1_1") (pintype "passive"))
      (node (ref "CN1") (pin "A13") (pinfunction "GND_A13") (pintype "passive"))
      (node (ref "CN1") (pin "A18") (pinfunction "GND_A18") (pintype "passive"))
      (node (ref "CN1") (pin "A23") (pinfunction "GND_A23") (pintype "passive"))
      (node (ref "CN1") (pin "A29") (pinfunction "GND_A29") (pintype "passive"))
      (node (ref "CN1") (pin "A36") (pinfunction "GND_A36") (pintype "passive"))
      (node (ref "CN1") (pin "A41") (pinfunction "GND_A41") (pintype "passive"))
      (node (ref "CN1") (pin "A46") (pinfunction "GND_A46") (pintype "passive"))
      (node (ref "CN1") (pin "A54") (pinfunction "GND_A54") (pintype "passive"))
      (node (ref "CN1") (pin "A59") (pinfunction "GND_A59") (pintype "passive"))
      (node (ref "CN1") (pin "A64") (pinfunction "GND_A64") (pintype "passive"))
      (node (ref "CN1") (pin "A65") (pinfunction "GND_A65") (pintype "passive"))
      (node (ref "CN1") (pin "A8") (pinfunction "GND_A8") (pintype "passive"))
      (node (ref "CN1") (pin "B13") (pinfunction "GND_B13") (pintype "passive"))
      (node (ref "CN1") (pin "B18") (pinfunction "GND_B18") (pintype "passive"))
      (node (ref "CN1") (pin "B23") (pinfunction "GND_B23") (pintype "passive"))
      (node (ref "CN1") (pin "B29") (pinfunction "GND_B29") (pintype "passive"))
      (node (ref "CN1") (pin "B36") (pinfunction "GND_B36") (pintype "passive"))
      (node (ref "CN1") (pin "B41") (pinfunction "GND_B41") (pintype "passive"))
      (node (ref "CN1") (pin "B46") (pinfunction "GND_B46") (pintype "passive"))
      (node (ref "CN1") (pin "B54") (pinfunction "GND_B54") (pintype "passive"))
      (node (ref "CN1") (pin "B59") (pinfunction "GND_B59") (pintype "passive"))
      (node (ref "CN1") (pin "B64") (pinfunction "GND_B64") (pintype "passive"))
      (node (ref "CN1") (pin "B65") (pinfunction "GND_B65") (pintype "passive"))
      (node (ref "CN1") (pin "B7") (pinfunction "GND_B7") (pintype "passive"))
      (node (ref "CN1") (pin "B8") (pinfunction "GND_B8") (pintype "passive"))
      (node (ref "U1") (pin "1") (pinfunction "1DIR_1") (pintype "passive"))
      (node (ref "U1") (pin "10") (pinfunction "GND_10") (pintype "power_in"))
      (node (ref "U1") (pin "15") (pinfunction "GND_15") (pintype "power_in"))
      (node (ref "U1") (pin "21") (pinfunction "GND_21") (pintype "power_in"))
      (node (ref "U1") (pin "24") (pinfunction "2DIR_24") (pintype "passive"))
      (node (ref "U1") (pin "25") (pinfunction "~{2OE}_25") (pintype "passive"))
      (node (ref "U1") (pin "28") (pinfunction "GND_28") (pintype "power_in"))
      (node (ref "U1") (pin "34") (pinfunction "GND_34") (pintype "power_in"))
      (node (ref "U1") (pin "39") (pinfunction "GND_39") (pintype "power_in"))
      (node (ref "U1") (pin "4") (pinfunction "GND_4") (pintype "power_in"))
      (node (ref "U1") (pin "45") (pinfunction "GND_45") (pintype "power_in"))
      (node (ref "U1") (pin "48") (pinfunction "~{1OE}_48") (pintype "passive"))
      (node (ref "U2") (pin "1") (pinfunction "1DIR_1") (pintype "passive"))
      (node (ref "U2") (pin "10") (pinfunction "GND_10") (pintype "power_in"))
      (node (ref "U2") (pin "15") (pinfunction "GND_15") (pintype "power_in"))
      (node (ref "U2") (pin "21") (pinfunction "GND_21") (pintype "power_in"))
      (node (ref "U2") (pin "24") (pinfunction "2DIR_24") (pintype "passive"))
      (node (ref "U2") (pin "25") (pinfunction "~{2OE}_25") (pintype "passive"))
      (node (ref "U2") (pin "28") (pinfunction "GND_28") (pintype "power_in"))
      (node (ref "U2") (pin "34") (pinfunction "GND_34") (pintype "power_in"))
      (node (ref "U2") (pin "39") (pinfunction "GND_39") (pintype "power_in"))
      (node (ref "U2") (pin "4") (pinfunction "GND_4") (pintype "power_in"))
      (node (ref "U2") (pin "45") (pinfunction "GND_45") (pintype "power_in"))
      (node (ref "U2") (pin "48") (pinfunction "~{1OE}_48") (pintype "passive"))
      (node (ref "U3") (pin "10") (pinfunction "GND_10") (pintype "power_in"))
      (node (ref "U3") (pin "15") (pinfunction "GND_15") (pintype "power_in"))
      (node (ref "U3") (pin "21") (pinfunction "GND_21") (pintype "power_in"))
      (node (ref "U3") (pin "28") (pinfunction "GND_28") (pintype "power_in"))
      (node (ref "U3") (pin "34") (pinfunction "GND_34") (pintype "power_in"))
      (node (ref "U3") (pin "39") (pinfunction "GND_39") (pintype "power_in"))
      (node (ref "U3") (pin "4") (pinfunction "GND_4") (pintype "power_in"))
      (node (ref "U3") (pin "45") (pinfunction "GND_45") (pintype "power_in"))
      (node (ref "U4") (pin "1") (pinfunction "1DIR_1") (pintype "passive"))
      (node (ref "U4") (pin "10") (pinfunction "GND_10") (pintype "power_in"))
      (node (ref "U4") (pin "15") (pinfunction "GND_15") (pintype "power_in"))
      (node (ref "U4") (pin "21") (pinfunction "GND_21") (pintype "power_in"))
      (node (ref "U4") (pin "28") (pinfunction "GND_28") (pintype "power_in"))
      (node (ref "U4") (pin "34") (pinfunction "GND_34") (pintype "power_in"))
      (node (ref "U4") (pin "39") (pinfunction "GND_39") (pintype "power_in"))
      (node (ref "U4") (pin "4") (pinfunction "GND_4") (pintype "power_in"))
      (node (ref "U4") (pin "45") (pinfunction "GND_45") (pintype "power_in"))
      (node (ref "U4") (pin "48") (pinfunction "~{1OE}_48") (pintype "passive"))
    )
    (net (code "131") (name "unconnected-(CN1-AA25-PadA31)") (class "Default")
      (node (ref "CN1") (pin "A31") (pinfunction "AA25_A31") (pintype "passive"))
    )
    (net (code "132") (name "unconnected-(CN1-CRTG0-PadA30)") (class "Default")
      (node (ref "CN1") (pin "A30") (pinfunction "CRTG0_A30") (pintype "passive"))
    )
    (net (code "133") (name "unconnected-(CN1-CRTG1-PadB30)") (class "Default")
      (node (ref "CN1") (pin "B30") (pinfunction "CRTG1_B30") (pintype "passive"))
    )
    (net (code "134") (name "unconnected-(CN1-DBCK-PadB5)") (class "Default")
      (node (ref "CN1") (pin "B5") (pinfunction "DBCK_B5") (pintype "passive"))
    )
    (net (code "135") (name "unconnected-(CN1-DLRCLK-PadB6)") (class "Default")
      (node (ref "CN1") (pin "B6") (pinfunction "DLRCLK_B6") (pintype "passive"))
    )
    (net (code "136") (name "unconnected-(CN1-DOTCLK-PadA28)") (class "Default")
      (node (ref "CN1") (pin "A28") (pinfunction "DOTCLK_A28") (pintype "passive"))
    )
    (net (code "137") (name "unconnected-(CN1-DSD-PadB4)") (class "Default")
      (node (ref "CN1") (pin "B4") (pinfunction "DSD_B4") (pintype "passive"))
    )
    (net (code "138") (name "unconnected-(CN1-ECBG1-PadB9)") (class "Default")
      (node (ref "CN1") (pin "B9") (pinfunction "ECBG1_B9") (pintype "passive"))
    )
    (net (code "139") (name "unconnected-(CN1-ECBG3-PadB10)") (class "Default")
      (node (ref "CN1") (pin "B10") (pinfunction "ECBG3_B10") (pintype "passive"))
    )
    (net (code "140") (name "unconnected-(CN1-ECBG5-PadB11)") (class "Default")
      (node (ref "CN1") (pin "B11") (pinfunction "ECBG5_B11") (pintype "passive"))
    )
    (net (code "141") (name "unconnected-(CN1-EXBG0-PadA9)") (class "Default")
      (node (ref "CN1") (pin "A9") (pinfunction "EXBG0_A9") (pintype "passive"))
    )
    (net (code "142") (name "unconnected-(CN1-EXBG2-PadA10)") (class "Default")
      (node (ref "CN1") (pin "A10") (pinfunction "EXBG2_A10") (pintype "passive"))
    )
    (net (code "143") (name "unconnected-(CN1-EXBG4-PadA11)") (class "Default")
      (node (ref "CN1") (pin "A11") (pinfunction "EXBG4_A11") (pintype "passive"))
    )
    (net (code "144") (name "unconnected-(CN1-EXBG6-PadA12)") (class "Default")
      (node (ref "CN1") (pin "A12") (pinfunction "EXBG6_A12") (pintype "passive"))
    )
    (net (code "145") (name "unconnected-(CN1-EXBG7-PadB12)") (class "Default")
      (node (ref "CN1") (pin "B12") (pinfunction "EXBG7_B12") (pintype "passive"))
    )
    (net (code "146") (name "unconnected-(CN1-EXBG8-PadA14)") (class "Default")
      (node (ref "CN1") (pin "A14") (pinfunction "EXBG8_A14") (pintype "passive"))
    )
    (net (code "147") (name "unconnected-(CN1-EXBG9-PadB14)") (class "Default")
      (node (ref "CN1") (pin "B14") (pinfunction "EXBG9_B14") (pintype "passive"))
    )
    (net (code "148") (name "unconnected-(CN1-EXBG10-PadA15)") (class "Default")
      (node (ref "CN1") (pin "A15") (pinfunction "EXBG10_A15") (pintype "passive"))
    )
    (net (code "149") (name "unconnected-(CN1-EXBG11-PadB15)") (class "Default")
      (node (ref "CN1") (pin "B15") (pinfunction "EXBG11_B15") (pintype "passive"))
    )
    (net (code "150") (name "unconnected-(CN1-EXBG12-PadA16)") (class "Default")
      (node (ref "CN1") (pin "A16") (pinfunction "EXBG12_A16") (pintype "passive"))
    )
    (net (code "151") (name "unconnected-(CN1-EXBG13-PadB16)") (class "Default")
      (node (ref "CN1") (pin "B16") (pinfunction "EXBG13_B16") (pintype "passive"))
    )
    (net (code "152") (name "unconnected-(CN1-EXBG14-PadA17)") (class "Default")
      (node (ref "CN1") (pin "A17") (pinfunction "EXBG14_A17") (pintype "passive"))
    )
    (net (code "153") (name "unconnected-(CN1-EXBG15-PadB17)") (class "Default")
      (node (ref "CN1") (pin "B17") (pinfunction "EXBG15_B17") (pintype "passive"))
    )
    (net (code "154") (name "unconnected-(CN1-EXBG16-PadA19)") (class "Default")
      (node (ref "CN1") (pin "A19") (pinfunction "EXBG16_A19") (pintype "passive"))
    )
    (net (code "155") (name "unconnected-(CN1-EXBG17-PadB19)") (class "Default")
      (node (ref "CN1") (pin "B19") (pinfunction "EXBG17_B19") (pintype "passive"))
    )
    (net (code "156") (name "unconnected-(CN1-EXBG18-PadA20)") (class "Default")
      (node (ref "CN1") (pin "A20") (pinfunction "EXBG18_A20") (pintype "passive"))
    )
    (net (code "157") (name "unconnected-(CN1-EXBG19-PadB20)") (class "Default")
      (node (ref "CN1") (pin "B20") (pinfunction "EXBG19_B20") (pintype "passive"))
    )
    (net (code "158") (name "unconnected-(CN1-EXBG20-PadA21)") (class "Default")
      (node (ref "CN1") (pin "A21") (pinfunction "EXBG20_A21") (pintype "passive"))
    )
    (net (code "159") (name "unconnected-(CN1-EXBG21-PadB21)") (class "Default")
      (node (ref "CN1") (pin "B21") (pinfunction "EXBG21_B21") (pintype "passive"))
    )
    (net (code "160") (name "unconnected-(CN1-EXBG22-PadA22)") (class "Default")
      (node (ref "CN1") (pin "A22") (pinfunction "EXBG22_A22") (pintype "passive"))
    )
    (net (code "161") (name "unconnected-(CN1-EXBG23-PadB22)") (class "Default")
      (node (ref "CN1") (pin "B22") (pinfunction "EXBG23_B22") (pintype "passive"))
    )
    (net (code "162") (name "unconnected-(CN1-~{COPRES}-PadA66)") (class "Default")
      (node (ref "CN1") (pin "A66") (pinfunction "~{COPRES}_A66") (pintype "passive"))
    )
    (net (code "163") (name "unconnected-(CN1-~{EXD}N-PadA24)") (class "Default")
      (node (ref "CN1") (pin "A24") (pinfunction "~{EXD}N_A24") (pintype "passive"))
    )
    (net (code "164") (name "unconnected-(CN1-~{EXLAT}-PadA25)") (class "Default")
      (node (ref "CN1") (pin "A25") (pinfunction "~{EXLAT}_A25") (pintype "passive"))
    )
    (net (code "165") (name "unconnected-(CN1-~{EXSL}-PadB25)") (class "Default")
      (node (ref "CN1") (pin "B25") (pinfunction "~{EXSL}_B25") (pintype "passive"))
    )
    (net (code "166") (name "unconnected-(CN1-~{EXSYNC}-PadB28)") (class "Default")
      (node (ref "CN1") (pin "B28") (pinfunction "~{EXSYNC}_B28") (pintype "passive"))
    )
    (net (code "167") (name "unconnected-(CN1-~{HSYNC}-PadA26)") (class "Default")
      (node (ref "CN1") (pin "A26") (pinfunction "~{HSYNC}_A26") (pintype "passive"))
    )
    (net (code "168") (name "unconnected-(CN1-~{MPEGON}-PadB24)") (class "Default")
      (node (ref "CN1") (pin "B24") (pinfunction "~{MPEGON}_B24") (pintype "passive"))
    )
    (net (code "169") (name "unconnected-(CN1-~{VSYNC}-PadB26)") (class "Default")
      (node (ref "CN1") (pin "B26") (pinfunction "~{VSYNC}_B26") (pintype "passive"))
    )
    (net (code "170") (name "unconnected-(U1-2A5-Pad30)") (class "Default")
      (node (ref "U1") (pin "30") (pinfunction "2A5_30") (pintype "passive"))
    )
    (net (code "171") (name "unconnected-(U1-2B5-Pad19)") (class "Default")
      (node (ref "U1") (pin "19") (pinfunction "2B5_19") (pintype "passive"))
    )
    (net (code "172") (name "unconnected-(U4-2A5-Pad30)") (class "Default")
      (node (ref "U4") (pin "30") (pinfunction "2A5_30") (pintype "passive"))
    )
    (net (code "173") (name "unconnected-(U4-2A6-Pad29)") (class "Default")
      (node (ref "U4") (pin "29") (pinfunction "2A6_29") (pintype "passive"))
    )
    (net (code "174") (name "unconnected-(U4-2B5-Pad19)") (class "Default")
      (node (ref "U4") (pin "19") (pinfunction "2B5_19") (pintype "passive"))
    )
    (net (code "175") (name "unconnected-(U4-2B6-Pad20)") (class "Default")
      (node (ref "U4") (pin "20") (pinfunction "2B6_20") (pintype "passive"))
    )
    (net (code "176") (name "unconnected-(U5D-IO,_DIFFIO_B13p-PadK9)") (class "Default")
      (node (ref "U5") (pin "K9") (pinfunction "IO,_DIFFIO_B13p_K9") (pintype "bidirectional"))
    )
    (net (code "177") (name "unconnected-(U5D-IO,_DIFFIO_B18p-PadK10)") (class "Default")
      (node (ref "U5") (pin "K10") (pinfunction "IO,_DIFFIO_B18p_K10") (pintype "bidirectional"))
    )
    (net (code "178") (name "unconnected-(U5D-IO,_DIFFIO_B21n-PadL11)") (class "Default")
      (node (ref "U5") (pin "L11") (pinfunction "IO,_DIFFIO_B21n_L11") (pintype "bidirectional"))
    )
    (net (code "179") (name "unconnected-(U5D-IO,_DIFFIO_B22p-PadM11)") (class "Default")
      (node (ref "U5") (pin "M11") (pinfunction "IO,_DIFFIO_B22p_M11") (pintype "bidirectional"))
    )
    (net (code "180") (name "unconnected-(U5E-IO-PadK11)") (class "Default")
      (node (ref "U5") (pin "K11") (pinfunction "IO_K11") (pintype "bidirectional"))
    )
  )
)
